# MCU.net
KiCad netlist of a schematic drawn in Altium Designer
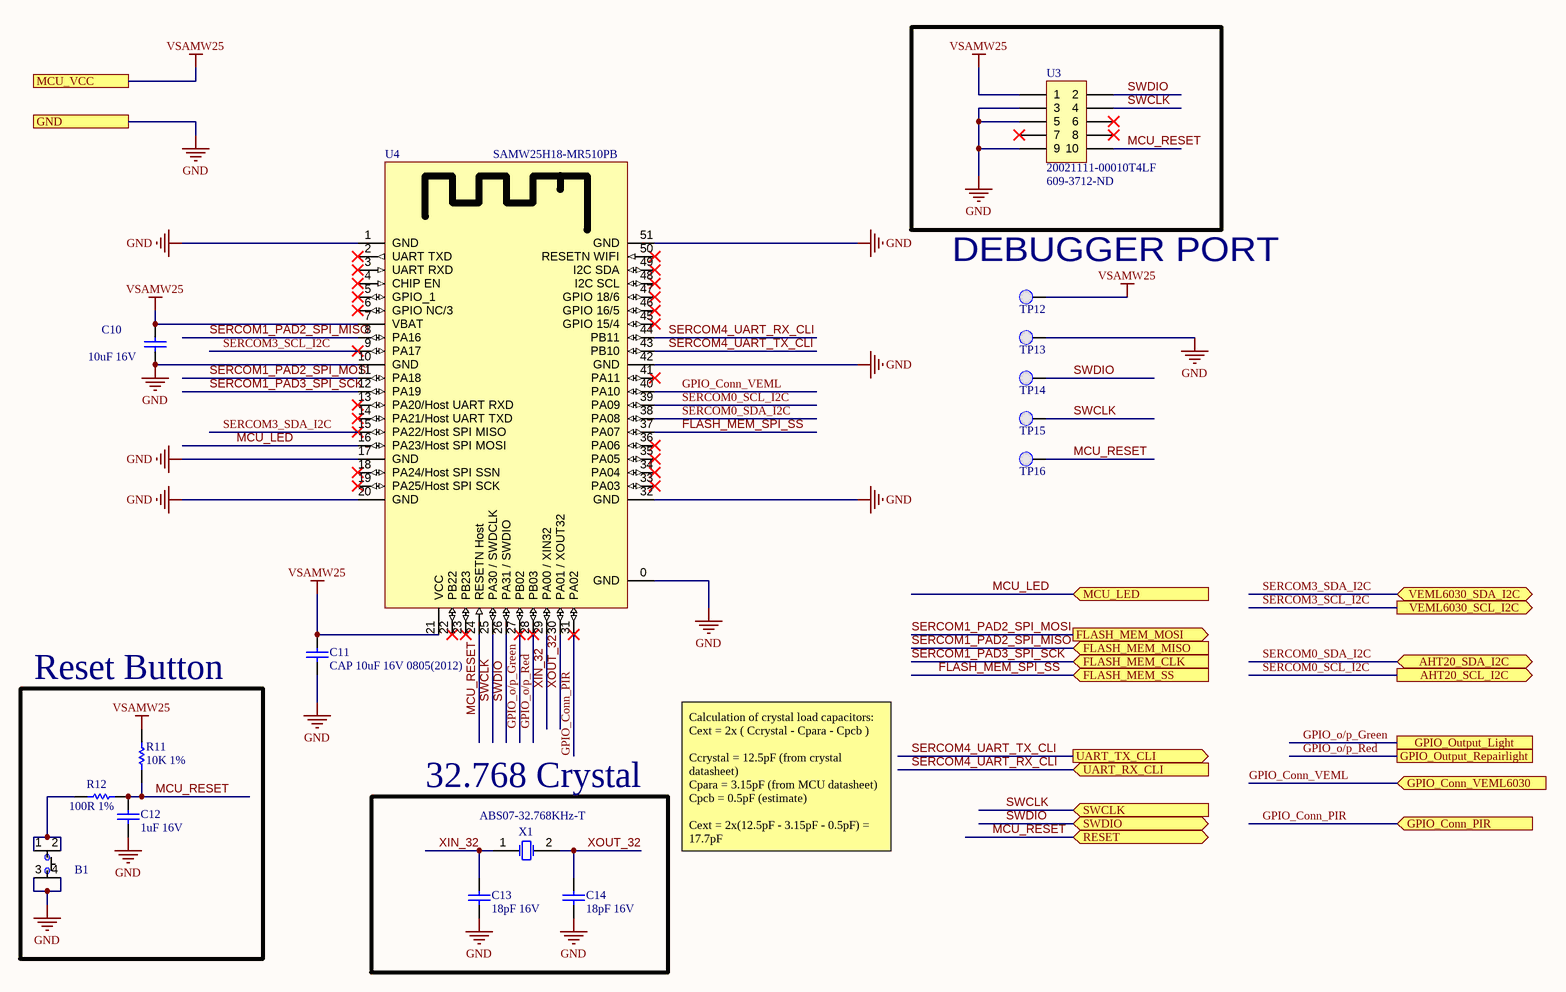
[diagram p0: MCU.SchDoc]

(export (version "E")
  (design (tool "Eeschema 10.0.6"))
  (components
    (comp (ref "B1")
      (value "PTS810 SJK 250 SMTR LFS")
      (footprint "PTS810 SJK 250 SMTR LFS")
      (description "SWITCH TACTILE SPST-NO 0.05A 16V Tactile Switch SPST-NO Top Actuated Surface Mount")
      (fields
        (field (name "MANUFACTURER") "ITT /  C&K Components")
        (field (name "MANUFACTURER PART NUMBER") "PTS810SJK250SMTRLFS")
      )
      (libsource (lib "Schematics") (part "PTS810 SJK 250 SMTR LFS"))
    )
    (comp (ref "C10")
      (value "10uF 16V")
      (footprint "CAPC0805(2012)145_N")
      (description "CAP 10uF 16V ±10% 0805 (2012 Metric) Thickness 1.45mm SMD")
      (fields (field (name "TOLERANCE") "Â±10%"))
      (libsource (lib "Altium Content Vault") (part "CAP"))
    )
    (comp (ref "C11")
      (value "CAP 10uF 16V 0805(2012)")
      (footprint "CAPC0805(2012)145_N")
      (description "CAP 10uF 16V ±10% 0805 (2012 Metric) Thickness 1.45mm SMD")
      (fields (field (name "TOLERANCE") "Â±10%"))
      (libsource (lib "Altium Content Vault") (part "CAP"))
    )
    (comp (ref "C12")
      (value "1uF 16V")
      (footprint "CAPC0603(1608)100_N")
      (description "CAP 1uF 16V ±5% 0603 (1608 Metric) Thickness 1mm SMD")
      (fields (field (name "TOLERANCE") "Â±5%"))
      (libsource (lib "Altium Content Vault") (part "CAP"))
    )
    (comp (ref "C13")
      (value "18pF 16V")
      (footprint "CAPC0603(1608)100_N")
      (description "CAP 18pF 16V ±5% 0603 (1608 Metric) Thickness 1mm SMD")
      (fields (field (name "TOLERANCE") "Â±5%"))
      (libsource (lib "Altium Content Vault") (part "CAP"))
    )
    (comp (ref "C14")
      (value "18pF 16V")
      (footprint "CAPC0603(1608)100_N")
      (description "CAP 18pF 16V ±5% 0603 (1608 Metric) Thickness 1mm SMD")
      (fields (field (name "TOLERANCE") "Â±5%"))
      (libsource (lib "Altium Content Vault") (part "CAP"))
    )
    (comp (ref "R11")
      (value "10K 1%")
      (footprint "RESC0603(1608)_N")
      (description "10K 0.1W 1% 0603 (1608 Metric)  SMD")
      (fields (field (name "POWER") "0.1 W") (field (name "TOLERANCE") "1 %"))
      (libsource (lib "Altium Content Vault") (part "RES"))
    )
    (comp (ref "R12")
      (value "100R 1%")
      (footprint "RESC0603(1608)_N")
      (description "100R 0.1W 1% 0603 (1608 Metric)  SMD")
      (fields (field (name "TOLERANCE") "1 %") (field (name "POWER") "0.1 W"))
      (libsource (lib "Altium Content Vault") (part "RES"))
    )
    (comp (ref "TP12")
      (value "0.1\" Pad")
      (footprint "PCBComponent")
      (libsource (lib "Components - 12.02.20 - 18.05") (part "0.1{dblquote} Pad-A.4"))
    )
    (comp (ref "TP13")
      (value "0.1\" Pad")
      (footprint "PCBComponent")
      (libsource (lib "Components - 12.02.20 - 18.05") (part "0.1{dblquote} Pad-A.4"))
    )
    (comp (ref "TP14")
      (value "0.1\" Pad")
      (footprint "PCBComponent")
      (libsource (lib "Components - 12.02.20 - 18.05") (part "0.1{dblquote} Pad-A.4"))
    )
    (comp (ref "TP15")
      (value "0.1\" Pad")
      (footprint "PCBComponent")
      (libsource (lib "Components - 12.02.20 - 18.05") (part "0.1{dblquote} Pad-A.4"))
    )
    (comp (ref "TP16")
      (value "0.1\" Pad")
      (footprint "PCBComponent")
      (libsource (lib "Components - 12.02.20 - 18.05") (part "0.1{dblquote} Pad-A.4"))
    )
    (comp (ref "U3")
      (value "20021111-00010T4LF")
      (footprint "20021111-00010T4LF")
      (description "CONN HEADER 10POS UNSHD VERT T/H")
      (fields
        (field (name "MANUFACTURER") "Amphenol / FCI")
        (field (name "SUPPLIER PART NUMBER 1") "609-3712-ND")
      )
      (libsource (lib "Schematics") (part "20021111-00010T4LF"))
    )
    (comp (ref "U4")
      (value "SAMW25H18-MR510PB")
      (footprint "SAMW25H18-MR510PB")
      (description "RF TXRX MODULE WIFI TRACE ANT")
      (fields
        (field (name "MANUFACTURER") "Atmel")
        (field (name "MANUFACTURER PART NUMBER") "ATSAMW25H18-MR510PB")
      )
      (libsource (lib "Schematics") (part "SAMW25H18-MR510PB"))
    )
    (comp (ref "X1")
      (value "ABS07-32.768KHz-T")
      (footprint "ABRA-ABS07-2_V")
      (description "Crystal, 32.768 kHz, 12.5 pF, -40 to 85 degC, SMD Low Profile 3.2 x 1.5 x 0.9 mm, Tape and Reel")
      (fields (field (name "MANUFACTURER") "Abracon"))
      (libsource (lib "Altium Content Vault") (part "ABRA-ABS07-2"))
    )
  )
  (nets
    (net (code "1") (name "/FLASH_MEM_SPI_SS") (class "Default")
      (node (ref "U4") (pin "37") (pinfunction "PA07_37") (pintype "bidirectional"))
    )
    (net (code "2") (name "/GPIO_Conn_PIR") (class "Default")
      (node (ref "U4") (pin "31") (pinfunction "PA02_31") (pintype "bidirectional+no_connect"))
    )
    (net (code "3") (name "/GPIO_Conn_VEML") (class "Default")
      (node (ref "U4") (pin "40") (pinfunction "PA10_40") (pintype "bidirectional"))
    )
    (net (code "4") (name "/GPIO_o{slash}p_Green") (class "Default")
      (node (ref "U4") (pin "27") (pinfunction "PB02_27") (pintype "bidirectional+no_connect"))
    )
    (net (code "5") (name "/GPIO_o{slash}p_Red") (class "Default")
      (node (ref "U4") (pin "28") (pinfunction "PB03_28") (pintype "bidirectional+no_connect"))
    )
    (net (code "6") (name "/MCU_LED") (class "Default")
      (node (ref "U4") (pin "16") (pinfunction "PA23/Host_SPI_MOSI_16") (pintype "bidirectional"))
    )
    (net (code "7") (name "/MCU_RESET") (class "Default")
      (node (ref "C12") (pin "2") (pinfunction "2_2") (pintype "passive"))
      (node (ref "R11") (pin "1") (pinfunction "1_1") (pintype "passive"))
      (node (ref "R12") (pin "2") (pinfunction "2_2") (pintype "passive"))
      (node (ref "TP16") (pin "1") (pinfunction "PAD_1") (pintype "passive"))
      (node (ref "U3") (pin "10") (pinfunction "10_10") (pintype "passive"))
      (node (ref "U4") (pin "24") (pinfunction "RESETN_Host_24") (pintype "input"))
    )
    (net (code "8") (name "/SERCOM0_SCL_I2C") (class "Default")
      (node (ref "U4") (pin "39") (pinfunction "PA09_39") (pintype "bidirectional"))
    )
    (net (code "9") (name "/SERCOM0_SDA_I2C") (class "Default")
      (node (ref "U4") (pin "38") (pinfunction "PA08_38") (pintype "bidirectional"))
    )
    (net (code "10") (name "/SERCOM1_PAD2_SPI_MISO") (class "Default")
      (node (ref "U4") (pin "8") (pinfunction "PA16_8") (pintype "bidirectional"))
    )
    (net (code "11") (name "/SERCOM1_PAD2_SPI_MOSI") (class "Default")
      (node (ref "U4") (pin "11") (pinfunction "PA18_11") (pintype "bidirectional"))
    )
    (net (code "12") (name "/SERCOM1_PAD3_SPI_SCK") (class "Default")
      (node (ref "U4") (pin "12") (pinfunction "PA19_12") (pintype "bidirectional"))
    )
    (net (code "13") (name "/SERCOM3_SCL_I2C") (class "Default")
      (node (ref "U4") (pin "9") (pinfunction "PA17_9") (pintype "bidirectional+no_connect"))
    )
    (net (code "14") (name "/SERCOM3_SDA_I2C") (class "Default")
      (node (ref "U4") (pin "15") (pinfunction "PA22/Host_SPI_MISO_15") (pintype "bidirectional+no_connect"))
    )
    (net (code "15") (name "/SERCOM4_UART_RX_CLI") (class "Default")
      (node (ref "U4") (pin "44") (pinfunction "PB11_44") (pintype "bidirectional"))
    )
    (net (code "16") (name "/SERCOM4_UART_TX_CLI") (class "Default")
      (node (ref "U4") (pin "43") (pinfunction "PB10_43") (pintype "bidirectional"))
    )
    (net (code "17") (name "/SWCLK") (class "Default")
      (node (ref "TP15") (pin "1") (pinfunction "PAD_1") (pintype "passive"))
      (node (ref "U3") (pin "4") (pinfunction "4_4") (pintype "passive"))
      (node (ref "U4") (pin "25") (pinfunction "PA30_/_SWDCLK_25") (pintype "bidirectional"))
    )
    (net (code "18") (name "/SWDIO") (class "Default")
      (node (ref "TP14") (pin "1") (pinfunction "PAD_1") (pintype "passive"))
      (node (ref "U3") (pin "2") (pinfunction "2_2") (pintype "passive"))
      (node (ref "U4") (pin "26") (pinfunction "PA31_/_SWDIO_26") (pintype "bidirectional"))
    )
    (net (code "19") (name "/XIN_32") (class "Default")
      (node (ref "C13") (pin "2") (pinfunction "2_2") (pintype "passive"))
      (node (ref "U4") (pin "29") (pinfunction "PA00_/_XIN32_29") (pintype "bidirectional"))
      (node (ref "X1") (pin "1") (pinfunction "X1_1") (pintype "passive"))
    )
    (net (code "20") (name "/XOUT_32") (class "Default")
      (node (ref "C14") (pin "2") (pinfunction "2_2") (pintype "passive"))
      (node (ref "U4") (pin "30") (pinfunction "PA01_/_XOUT32_30") (pintype "bidirectional"))
      (node (ref "X1") (pin "2") (pinfunction "X2_2") (pintype "passive"))
    )
    (net (code "21") (name "GND") (class "Default")
      (node (ref "B1") (pin "3") (pinfunction "3_3") (pintype "power_in"))
      (node (ref "B1") (pin "4") (pinfunction "4_4") (pintype "power_in"))
      (node (ref "C10") (pin "1") (pinfunction "1_1") (pintype "passive"))
      (node (ref "C11") (pin "1") (pinfunction "1_1") (pintype "passive"))
      (node (ref "C12") (pin "1") (pinfunction "1_1") (pintype "passive"))
      (node (ref "C13") (pin "1") (pinfunction "1_1") (pintype "passive"))
      (node (ref "C14") (pin "1") (pinfunction "1_1") (pintype "passive"))
      (node (ref "TP13") (pin "1") (pinfunction "PAD_1") (pintype "passive"))
      (node (ref "U3") (pin "3") (pinfunction "3_3") (pintype "passive"))
      (node (ref "U3") (pin "5") (pinfunction "5_5") (pintype "passive"))
      (node (ref "U3") (pin "9") (pinfunction "9_9") (pintype "passive"))
      (node (ref "U4") (pin "0") (pinfunction "GND_0") (pintype "power_in"))
      (node (ref "U4") (pin "1") (pinfunction "GND_1") (pintype "power_in"))
      (node (ref "U4") (pin "10") (pinfunction "GND_10") (pintype "power_in"))
      (node (ref "U4") (pin "17") (pinfunction "GND_17") (pintype "power_in"))
      (node (ref "U4") (pin "20") (pinfunction "GND_20") (pintype "power_in"))
      (node (ref "U4") (pin "32") (pinfunction "GND_32") (pintype "power_in"))
      (node (ref "U4") (pin "42") (pinfunction "GND_42") (pintype "power_in"))
      (node (ref "U4") (pin "51") (pinfunction "GND_51") (pintype "power_in"))
    )
    (net (code "22") (name "Net-(B1-Pad1)") (class "Default")
      (node (ref "B1") (pin "1") (pinfunction "1_1") (pintype "power_in"))
      (node (ref "B1") (pin "2") (pinfunction "2_2") (pintype "power_in"))
      (node (ref "R12") (pin "1") (pinfunction "1_1") (pintype "passive"))
    )
    (net (code "23") (name "VSAMW25") (class "Default")
      (node (ref "C10") (pin "2") (pinfunction "2_2") (pintype "passive"))
      (node (ref "C11") (pin "2") (pinfunction "2_2") (pintype "passive"))
      (node (ref "R11") (pin "2") (pinfunction "2_2") (pintype "passive"))
      (node (ref "TP12") (pin "1") (pinfunction "PAD_1") (pintype "passive"))
      (node (ref "U3") (pin "1") (pinfunction "1_1") (pintype "passive"))
      (node (ref "U4") (pin "21") (pinfunction "VCC_21") (pintype "power_in"))
      (node (ref "U4") (pin "7") (pinfunction "VBAT_7") (pintype "power_in"))
    )
    (net (code "24") (name "unconnected-(U3-Pad6)") (class "Default")
      (node (ref "U3") (pin "6") (pinfunction "6_6") (pintype "passive+no_connect"))
    )
    (net (code "25") (name "unconnected-(U3-Pad7)") (class "Default")
      (node (ref "U3") (pin "7") (pinfunction "7_7") (pintype "passive+no_connect"))
    )
    (net (code "26") (name "unconnected-(U3-Pad8)") (class "Default")
      (node (ref "U3") (pin "8") (pinfunction "8_8") (pintype "passive+no_connect"))
    )
    (net (code "27") (name "unconnected-(U4-CHIP_EN-Pad4)") (class "Default")
      (node (ref "U4") (pin "4") (pinfunction "CHIP_EN_4") (pintype "input+no_connect"))
    )
    (net (code "28") (name "unconnected-(U4-GPIO_1-Pad5)") (class "Default")
      (node (ref "U4") (pin "5") (pinfunction "GPIO_1_5") (pintype "bidirectional+no_connect"))
    )
    (net (code "29") (name "unconnected-(U4-GPIO_15{slash}4-Pad45)") (class "Default")
      (node (ref "U4") (pin "45") (pinfunction "GPIO_15/4_45") (pintype "bidirectional+no_connect"))
    )
    (net (code "30") (name "unconnected-(U4-GPIO_16{slash}5-Pad46)") (class "Default")
      (node (ref "U4") (pin "46") (pinfunction "GPIO_16/5_46") (pintype "bidirectional+no_connect"))
    )
    (net (code "31") (name "unconnected-(U4-GPIO_18{slash}6-Pad47)") (class "Default")
      (node (ref "U4") (pin "47") (pinfunction "GPIO_18/6_47") (pintype "bidirectional+no_connect"))
    )
    (net (code "32") (name "unconnected-(U4-GPIO_NC{slash}3-Pad6)") (class "Default")
      (node (ref "U4") (pin "6") (pinfunction "GPIO_NC/3_6") (pintype "bidirectional+no_connect"))
    )
    (net (code "33") (name "unconnected-(U4-I2C_SCL-Pad48)") (class "Default")
      (node (ref "U4") (pin "48") (pinfunction "I2C_SCL_48") (pintype "bidirectional+no_connect"))
    )
    (net (code "34") (name "unconnected-(U4-I2C_SDA-Pad49)") (class "Default")
      (node (ref "U4") (pin "49") (pinfunction "I2C_SDA_49") (pintype "bidirectional+no_connect"))
    )
    (net (code "35") (name "unconnected-(U4-PA03-Pad33)") (class "Default")
      (node (ref "U4") (pin "33") (pinfunction "PA03_33") (pintype "bidirectional+no_connect"))
    )
    (net (code "36") (name "unconnected-(U4-PA04-Pad34)") (class "Default")
      (node (ref "U4") (pin "34") (pinfunction "PA04_34") (pintype "bidirectional+no_connect"))
    )
    (net (code "37") (name "unconnected-(U4-PA05-Pad35)") (class "Default")
      (node (ref "U4") (pin "35") (pinfunction "PA05_35") (pintype "bidirectional+no_connect"))
    )
    (net (code "38") (name "unconnected-(U4-PA06-Pad36)") (class "Default")
      (node (ref "U4") (pin "36") (pinfunction "PA06_36") (pintype "bidirectional+no_connect"))
    )
    (net (code "39") (name "unconnected-(U4-PA11-Pad41)") (class "Default")
      (node (ref "U4") (pin "41") (pinfunction "PA11_41") (pintype "bidirectional+no_connect"))
    )
    (net (code "40") (name "unconnected-(U4-PA20{slash}Host_UART_RXD-Pad13)") (class "Default")
      (node (ref "U4") (pin "13") (pinfunction "PA20/Host_UART_RXD_13") (pintype "bidirectional+no_connect"))
    )
    (net (code "41") (name "unconnected-(U4-PA21{slash}Host_UART_TXD-Pad14)") (class "Default")
      (node (ref "U4") (pin "14") (pinfunction "PA21/Host_UART_TXD_14") (pintype "bidirectional+no_connect"))
    )
    (net (code "42") (name "unconnected-(U4-PA24{slash}Host_SPI_SSN-Pad18)") (class "Default")
      (node (ref "U4") (pin "18") (pinfunction "PA24/Host_SPI_SSN_18") (pintype "bidirectional+no_connect"))
    )
    (net (code "43") (name "unconnected-(U4-PA25{slash}Host_SPI_SCK-Pad19)") (class "Default")
      (node (ref "U4") (pin "19") (pinfunction "PA25/Host_SPI_SCK_19") (pintype "bidirectional+no_connect"))
    )
    (net (code "44") (name "unconnected-(U4-PB22-Pad22)") (class "Default")
      (node (ref "U4") (pin "22") (pinfunction "PB22_22") (pintype "bidirectional+no_connect"))
    )
    (net (code "45") (name "unconnected-(U4-PB23-Pad23)") (class "Default")
      (node (ref "U4") (pin "23") (pinfunction "PB23_23") (pintype "bidirectional+no_connect"))
    )
    (net (code "46") (name "unconnected-(U4-RESETN_WIFI-Pad50)") (class "Default")
      (node (ref "U4") (pin "50") (pinfunction "RESETN_WIFI_50") (pintype "input+no_connect"))
    )
    (net (code "47") (name "unconnected-(U4-UART_RXD-Pad3)") (class "Default")
      (node (ref "U4") (pin "3") (pinfunction "UART_RXD_3") (pintype "input+no_connect"))
    )
    (net (code "48") (name "unconnected-(U4-UART_TXD-Pad2)") (class "Default")
      (node (ref "U4") (pin "2") (pinfunction "UART_TXD_2") (pintype "output+no_connect"))
    )
  )
)
